# Support.net
KiCad netlist of a schematic drawn in Altium Designer
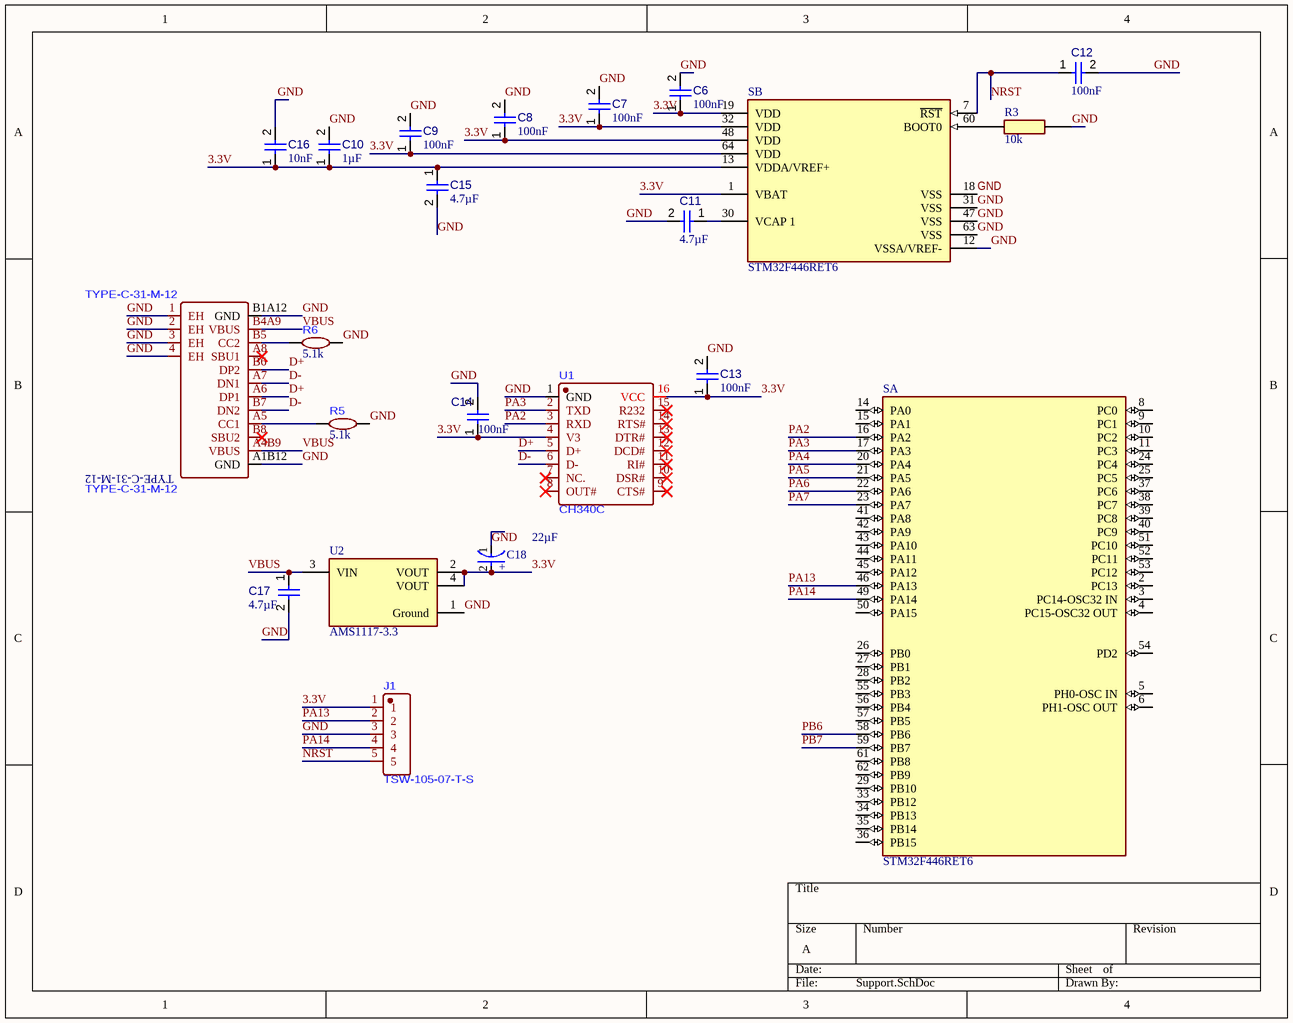
[diagram p0: Support.SchDoc]

(export (version "E")
  (design (tool "Eeschema 10.0.6"))
  (components
    (comp (ref "C6")
      (value "100nF")
      (footprint "CAPC1608X90X40NL10T20")
      (description "Chip Capacitor, 100 nF, +/- 10%, 50 V, 0603 (1608 Metric)")
      (fields (field (name "TOLERANCE") "10%") (field (name "Comment") "Capacitor 100 nF +/-10% 50 V 0603"))
      (libsource (lib "Jegasoth") (part "CAP-NP-2"))
    )
    (comp (ref "C7")
      (value "100nF")
      (footprint "CAPC1608X90X40NL10T20")
      (description "Chip Capacitor, 100 nF, +/- 10%, 50 V, 0603 (1608 Metric)")
      (fields (field (name "TOLERANCE") "10%") (field (name "Comment") "Capacitor 100 nF +/-10% 50 V 0603"))
      (libsource (lib "Jegasoth") (part "CAP-NP-2"))
    )
    (comp (ref "C8")
      (value "100nF")
      (footprint "CAPC1608X90X40NL10T20")
      (description "Chip Capacitor, 100 nF, +/- 10%, 50 V, 0603 (1608 Metric)")
      (fields (field (name "TOLERANCE") "10%") (field (name "Comment") "Capacitor 100 nF +/-10% 50 V 0603"))
      (libsource (lib "Jegasoth") (part "CAP-NP-2"))
    )
    (comp (ref "C9")
      (value "100nF")
      (footprint "CAPC1608X90X40NL10T20")
      (description "Chip Capacitor, 100 nF, +/- 10%, 50 V, 0603 (1608 Metric)")
      (fields (field (name "TOLERANCE") "10%") (field (name "Comment") "Capacitor 100 nF +/-10% 50 V 0603"))
      (libsource (lib "Jegasoth") (part "CAP-NP-2"))
    )
    (comp (ref "C10")
      (value "1µF")
      (footprint "CAPC0603(1608)100_L")
      (description "Chip Capacitor, 1µF +/-40%, 50V, 0603, Thickness 1 mm")
      (fields (field (name "TOLERANCE") "10%") (field (name "Comment") "Capacitor 1µF +/-40% 50V 0603"))
      (libsource (lib "Jegasoth") (part "CAP-NP-2"))
    )
    (comp (ref "C11")
      (value "4.7µF")
      (footprint "CAPC0603(1608)100_L")
      (description "Chip Capacitor, 4.7µF +/-20%, 10V, 0603, Thickness 1 mm")
      (fields (field (name "TOLERANCE") "10%") (field (name "Comment") "Capacitor 4.7µF +/-20% 10V 0603"))
      (libsource (lib "Jegasoth") (part "CAP-NP-2"))
    )
    (comp (ref "C12")
      (value "100nF")
      (footprint "CAPC1608X90X40NL10T20")
      (description "Chip Capacitor, 100 nF, +/- 10%, 50 V, 0603 (1608 Metric)")
      (fields (field (name "TOLERANCE") "10%") (field (name "Comment") "Capacitor 100 nF +/-10% 50 V 0603"))
      (libsource (lib "Jegasoth") (part "CAP-NP-2"))
    )
    (comp (ref "C13")
      (value "100nF")
      (footprint "CAPC1608X90X40NL10T20")
      (description "Chip Capacitor, 100 nF, +/- 10%, 50 V, 0603 (1608 Metric)")
      (fields (field (name "TOLERANCE") "10%") (field (name "Comment") "Capacitor 100 nF +/-10% 50 V 0603"))
      (libsource (lib "Jegasoth") (part "CAP-NP-2"))
    )
    (comp (ref "C14")
      (value "100nF")
      (footprint "CAPC1608X90X40NL10T20")
      (description "Chip Capacitor, 100 nF, +/- 10%, 50 V, 0603 (1608 Metric)")
      (fields (field (name "TOLERANCE") "10%") (field (name "Comment") "Capacitor 100 nF +/-10% 50 V 0603"))
      (libsource (lib "Jegasoth") (part "CAP-NP-2"))
    )
    (comp (ref "C15")
      (value "4.7µF")
      (footprint "CAPC0603(1608)100_L")
      (description "Chip Capacitor, 4.7µF +/-20%, 10V, 0603, Thickness 1 mm")
      (fields (field (name "TOLERANCE") "10%") (field (name "Comment") "Capacitor 4.7µF +/-20% 10V 0603"))
      (libsource (lib "Jegasoth") (part "CAP-NP-2"))
    )
    (comp (ref "C16")
      (value "10nF")
      (footprint "CAPC0402(1005)60_L")
      (description "Chip Capacitor, 10nF +/-20%, 50V, 0402, Thickness 0.6 mm")
      (fields (field (name "TOLERANCE") "5%") (field (name "Comment") "Capacitor 10nF +/-20% 50V 0402"))
      (libsource (lib "Jegasoth") (part "CAP-NP-2"))
    )
    (comp (ref "C17")
      (value "4.7µF")
      (footprint "CAPC0603(1608)100_L")
      (description "Chip Capacitor, 4.7µF +/-20%, 10V, 0603, Thickness 1 mm")
      (fields (field (name "TOLERANCE") "10%") (field (name "Comment") "Capacitor 4.7µF +/-20% 10V 0603"))
      (libsource (lib "Jegasoth") (part "CAP-NP-2"))
    )
    (comp (ref "C18")
      (value "22µF")
      (footprint "FP-TAJA-MFG")
      (description "Cap Tant Solid 22uF 10V A CASE 20%( 3.2 X 1.6 X 1.6mm) Inward L SMD 3216-18 3 Ohm 125C T/R")
      (fields (field (name "TOLERANCE") "20%") (field (name "VOLTAGE") "10V"))
      (libsource (lib "Jegasoth") (part "203bc49f2ac43e59fd269a8c329ed05"))
    )
    (comp (ref "J1")
      (value "TSW-105-07-T-S")
      (footprint "PCBComponent_1")
      (description "CONN HEADER VERT 5POS 2.54MM / Connector Header Through Hole 5 position 0.100\" (2.54mm)")
      (libsource (lib "Jegasoth") (part "TSW-105-07-T-S"))
    )
    (comp (ref "R3")
      (value "10k")
      (footprint "RESC1005X40N")
      (description "Res Thick Film 0402 10K Ohm 1% 0.063W(1/16W) ±100ppm/C Pad SMD T/R")
      (fields (field (name "TOLERANCE") "1%") (field (name "Comment") "0402WGF1002TCE"))
      (libsource (lib "Jegasoth") (part "0402WGF1002TCE"))
    )
    (comp (ref "R5")
      (value "5.1k")
      (footprint "PCBComponent_1")
      (description "Res Thick Film 0603 5.1K Ohm 1% 0.1W(1/10W) ±100ppm/C Pad SMD T/R")
      (fields (field (name "Comment") "0603WAF5101T5E"))
      (libsource (lib "Jegasoth") (part "0603WAF5101T5E"))
    )
    (comp (ref "R6")
      (value "5.1k")
      (footprint "PCBComponent_1")
      (description "Res Thick Film 0603 5.1K Ohm 1% 0.1W(1/10W) ±100ppm/C Pad SMD T/R")
      (fields (field (name "Comment") "0603WAF5101T5E"))
      (libsource (lib "Jegasoth") (part "0603WAF5101T5E"))
    )
    (comp (ref "S")
      (value "STM32F446RET6")
      (footprint "FP-LQFP64-5W-MFG")
      (description "MCU 32-bit ARM Cortex M4 RISC 512KB Flash 2.5V/3.3V Medical 64-Pin LQFP Frame")
      (libsource (lib "Jegasoth") (part "ee11adc32c0ab33b933cccf4348c338"))
    )
    (comp (ref "TYPE-C-31-M-12")
      (value "TYPE-C-31-M-12")
      (footprint "PCBComponent_1")
      (description "20V Type-C 1 16P Female head")
      (libsource (lib "Jegasoth") (part "TYPE-C-31-M-12_4"))
    )
    (comp (ref "U1")
      (value "CH340C")
      (footprint "PCBComponent_1")
      (description "uart to usb c")
      (libsource (lib "Jegasoth") (part "CH340C"))
    )
    (comp (ref "U2")
      (value "AMS1117-3.3")
      (footprint "FP-AMS1117-IPC_A")
      (libsource (lib "Jegasoth") (part "8bdbb5f8e77002000e30dd2845d0354"))
    )
  )
  (nets
    (net (code "1") (name "/3.3V") (class "Default")
      (node (ref "C10") (pin "1") (pinfunction "1_1") (pintype "passive"))
      (node (ref "C13") (pin "1") (pinfunction "1_1") (pintype "passive"))
      (node (ref "C14") (pin "1") (pinfunction "1_1") (pintype "passive"))
      (node (ref "C15") (pin "1") (pinfunction "1_1") (pintype "passive"))
      (node (ref "C16") (pin "1") (pinfunction "1_1") (pintype "passive"))
      (node (ref "C18") (pin "2") (pinfunction "A_2") (pintype "passive"))
      (node (ref "C6") (pin "1") (pinfunction "1_1") (pintype "passive"))
      (node (ref "C7") (pin "1") (pinfunction "1_1") (pintype "passive"))
      (node (ref "C8") (pin "1") (pinfunction "1_1") (pintype "passive"))
      (node (ref "C9") (pin "1") (pinfunction "1_1") (pintype "passive"))
      (node (ref "J1") (pin "1") (pinfunction "1_1") (pintype "passive"))
      (node (ref "S") (pin "1") (pinfunction "VBAT_1") (pintype "power_in"))
      (node (ref "S") (pin "13") (pinfunction "VDDA/VREF+_13") (pintype "power_in"))
      (node (ref "S") (pin "19") (pinfunction "VDD_19") (pintype "power_in"))
      (node (ref "S") (pin "32") (pinfunction "VDD_32") (pintype "power_in"))
      (node (ref "S") (pin "48") (pinfunction "VDD_48") (pintype "power_in"))
      (node (ref "S") (pin "64") (pinfunction "VDD_64") (pintype "power_in"))
      (node (ref "U1") (pin "16") (pinfunction "VCC_16") (pintype "passive"))
      (node (ref "U1") (pin "4") (pinfunction "V3_4") (pintype "passive"))
      (node (ref "U2") (pin "2") (pinfunction "VOUT_2") (pintype "passive"))
      (node (ref "U2") (pin "4") (pinfunction "VOUT_4") (pintype "passive"))
    )
    (net (code "2") (name "/D+") (class "Default")
      (node (ref "TYPE-C-31-M-12") (pin "A6") (pinfunction "DP1_A6") (pintype "passive"))
      (node (ref "TYPE-C-31-M-12") (pin "B6") (pinfunction "DP2_B6") (pintype "passive"))
      (node (ref "U1") (pin "5") (pinfunction "D+_5") (pintype "passive"))
    )
    (net (code "3") (name "/D-") (class "Default")
      (node (ref "TYPE-C-31-M-12") (pin "A7") (pinfunction "DN1_A7") (pintype "passive"))
      (node (ref "TYPE-C-31-M-12") (pin "B7") (pinfunction "DN2_B7") (pintype "passive"))
      (node (ref "U1") (pin "6") (pinfunction "D-_6") (pintype "passive"))
    )
    (net (code "4") (name "/GND") (class "Default")
      (node (ref "C10") (pin "2") (pinfunction "2_2") (pintype "passive"))
      (node (ref "C11") (pin "2") (pinfunction "2_2") (pintype "passive"))
      (node (ref "C12") (pin "2") (pinfunction "2_2") (pintype "passive"))
      (node (ref "C13") (pin "2") (pinfunction "2_2") (pintype "passive"))
      (node (ref "C14") (pin "2") (pinfunction "2_2") (pintype "passive"))
      (node (ref "C15") (pin "2") (pinfunction "2_2") (pintype "passive"))
      (node (ref "C16") (pin "2") (pinfunction "2_2") (pintype "passive"))
      (node (ref "C17") (pin "2") (pinfunction "2_2") (pintype "passive"))
      (node (ref "C18") (pin "1") (pinfunction "C_1") (pintype "passive"))
      (node (ref "C6") (pin "2") (pinfunction "2_2") (pintype "passive"))
      (node (ref "C7") (pin "2") (pinfunction "2_2") (pintype "passive"))
      (node (ref "C8") (pin "2") (pinfunction "2_2") (pintype "passive"))
      (node (ref "C9") (pin "2") (pinfunction "2_2") (pintype "passive"))
      (node (ref "J1") (pin "3") (pinfunction "3_3") (pintype "passive"))
      (node (ref "R3") (pin "2") (pinfunction "2_2") (pintype "passive"))
      (node (ref "R5") (pin "2") (pinfunction "2_2") (pintype "passive"))
      (node (ref "R6") (pin "2") (pinfunction "2_2") (pintype "passive"))
      (node (ref "S") (pin "12") (pinfunction "VSSA/VREF-_12") (pintype "power_in"))
      (node (ref "S") (pin "18") (pinfunction "VSS_18") (pintype "power_in"))
      (node (ref "S") (pin "31") (pinfunction "VSS_31") (pintype "power_in"))
      (node (ref "S") (pin "47") (pinfunction "VSS_47") (pintype "power_in"))
      (node (ref "S") (pin "63") (pinfunction "VSS_63") (pintype "power_in"))
      (node (ref "TYPE-C-31-M-12") (pin "1") (pinfunction "EH_1") (pintype "passive"))
      (node (ref "TYPE-C-31-M-12") (pin "2") (pinfunction "EH_2") (pintype "passive"))
      (node (ref "TYPE-C-31-M-12") (pin "3") (pinfunction "EH_3") (pintype "passive"))
      (node (ref "TYPE-C-31-M-12") (pin "4") (pinfunction "EH_4") (pintype "passive"))
      (node (ref "TYPE-C-31-M-12") (pin "A1B12") (pinfunction "GND_A1B12") (pintype "passive"))
      (node (ref "TYPE-C-31-M-12") (pin "B1A12") (pinfunction "GND_B1A12") (pintype "passive"))
      (node (ref "U1") (pin "1") (pinfunction "GND_1") (pintype "passive"))
      (node (ref "U2") (pin "1") (pinfunction "Ground_1") (pintype "power_in"))
    )
    (net (code "5") (name "/NRST") (class "Default")
      (node (ref "C12") (pin "1") (pinfunction "1_1") (pintype "passive"))
      (node (ref "J1") (pin "5") (pinfunction "5_5") (pintype "passive"))
      (node (ref "S") (pin "7") (pinfunction "~{RST}_7") (pintype "input"))
    )
    (net (code "6") (name "/PA2") (class "Default")
      (node (ref "S") (pin "16") (pinfunction "PA2_16") (pintype "bidirectional"))
      (node (ref "U1") (pin "3") (pinfunction "RXD_3") (pintype "passive"))
    )
    (net (code "7") (name "/PA3") (class "Default")
      (node (ref "S") (pin "17") (pinfunction "PA3_17") (pintype "bidirectional"))
      (node (ref "U1") (pin "2") (pinfunction "TXD_2") (pintype "passive"))
    )
    (net (code "8") (name "/PA4") (class "Default")
      (node (ref "S") (pin "20") (pinfunction "PA4_20") (pintype "bidirectional"))
    )
    (net (code "9") (name "/PA5") (class "Default")
      (node (ref "S") (pin "21") (pinfunction "PA5_21") (pintype "bidirectional"))
    )
    (net (code "10") (name "/PA6") (class "Default")
      (node (ref "S") (pin "22") (pinfunction "PA6_22") (pintype "bidirectional"))
    )
    (net (code "11") (name "/PA7") (class "Default")
      (node (ref "S") (pin "23") (pinfunction "PA7_23") (pintype "bidirectional"))
    )
    (net (code "12") (name "/PA13") (class "Default")
      (node (ref "J1") (pin "2") (pinfunction "2_2") (pintype "passive"))
      (node (ref "S") (pin "46") (pinfunction "PA13_46") (pintype "bidirectional"))
    )
    (net (code "13") (name "/PA14") (class "Default")
      (node (ref "J1") (pin "4") (pinfunction "4_4") (pintype "passive"))
      (node (ref "S") (pin "49") (pinfunction "PA14_49") (pintype "bidirectional"))
    )
    (net (code "14") (name "/PB6") (class "Default")
      (node (ref "S") (pin "58") (pinfunction "PB6_58") (pintype "bidirectional"))
    )
    (net (code "15") (name "/PB7") (class "Default")
      (node (ref "S") (pin "59") (pinfunction "PB7_59") (pintype "bidirectional"))
    )
    (net (code "16") (name "/VBUS") (class "Default")
      (node (ref "C17") (pin "1") (pinfunction "1_1") (pintype "passive"))
      (node (ref "TYPE-C-31-M-12") (pin "A4B9") (pinfunction "VBUS_A4B9") (pintype "passive"))
      (node (ref "TYPE-C-31-M-12") (pin "B4A9") (pinfunction "VBUS_B4A9") (pintype "passive"))
      (node (ref "U2") (pin "3") (pinfunction "VIN_3") (pintype "power_in"))
    )
    (net (code "17") (name "Net-(SB-BOOT0)") (class "Default")
      (node (ref "R3") (pin "1") (pinfunction "1_1") (pintype "passive"))
      (node (ref "S") (pin "60") (pinfunction "BOOT0_60") (pintype "input"))
    )
    (net (code "18") (name "Net-(SB-VCAP_1)") (class "Default")
      (node (ref "C11") (pin "1") (pinfunction "1_1") (pintype "passive"))
      (node (ref "S") (pin "30") (pinfunction "VCAP_1_30") (pintype "power_in"))
    )
    (net (code "19") (name "Net-(TYPE-C-31-M-12-CC1)") (class "Default")
      (node (ref "R5") (pin "1") (pinfunction "1_1") (pintype "passive"))
      (node (ref "TYPE-C-31-M-12") (pin "A5") (pinfunction "CC1_A5") (pintype "passive"))
    )
    (net (code "20") (name "Net-(TYPE-C-31-M-12-CC2)") (class "Default")
      (node (ref "R6") (pin "1") (pinfunction "1_1") (pintype "passive"))
      (node (ref "TYPE-C-31-M-12") (pin "B5") (pinfunction "CC2_B5") (pintype "passive"))
    )
    (net (code "21") (name "unconnected-(SA-PA0-Pad14)") (class "Default")
      (node (ref "S") (pin "14") (pinfunction "PA0_14") (pintype "bidirectional"))
    )
    (net (code "22") (name "unconnected-(SA-PA1-Pad15)") (class "Default")
      (node (ref "S") (pin "15") (pinfunction "PA1_15") (pintype "bidirectional"))
    )
    (net (code "23") (name "unconnected-(SA-PA8-Pad41)") (class "Default")
      (node (ref "S") (pin "41") (pinfunction "PA8_41") (pintype "bidirectional"))
    )
    (net (code "24") (name "unconnected-(SA-PA9-Pad42)") (class "Default")
      (node (ref "S") (pin "42") (pinfunction "PA9_42") (pintype "bidirectional"))
    )
    (net (code "25") (name "unconnected-(SA-PA10-Pad43)") (class "Default")
      (node (ref "S") (pin "43") (pinfunction "PA10_43") (pintype "bidirectional"))
    )
    (net (code "26") (name "unconnected-(SA-PA11-Pad44)") (class "Default")
      (node (ref "S") (pin "44") (pinfunction "PA11_44") (pintype "bidirectional"))
    )
    (net (code "27") (name "unconnected-(SA-PA12-Pad45)") (class "Default")
      (node (ref "S") (pin "45") (pinfunction "PA12_45") (pintype "bidirectional"))
    )
    (net (code "28") (name "unconnected-(SA-PA15-Pad50)") (class "Default")
      (node (ref "S") (pin "50") (pinfunction "PA15_50") (pintype "bidirectional"))
    )
    (net (code "29") (name "unconnected-(SA-PB0-Pad26)") (class "Default")
      (node (ref "S") (pin "26") (pinfunction "PB0_26") (pintype "bidirectional"))
    )
    (net (code "30") (name "unconnected-(SA-PB1-Pad27)") (class "Default")
      (node (ref "S") (pin "27") (pinfunction "PB1_27") (pintype "bidirectional"))
    )
    (net (code "31") (name "unconnected-(SA-PB2-Pad28)") (class "Default")
      (node (ref "S") (pin "28") (pinfunction "PB2_28") (pintype "bidirectional"))
    )
    (net (code "32") (name "unconnected-(SA-PB3-Pad55)") (class "Default")
      (node (ref "S") (pin "55") (pinfunction "PB3_55") (pintype "bidirectional"))
    )
    (net (code "33") (name "unconnected-(SA-PB4-Pad56)") (class "Default")
      (node (ref "S") (pin "56") (pinfunction "PB4_56") (pintype "bidirectional"))
    )
    (net (code "34") (name "unconnected-(SA-PB5-Pad57)") (class "Default")
      (node (ref "S") (pin "57") (pinfunction "PB5_57") (pintype "bidirectional"))
    )
    (net (code "35") (name "unconnected-(SA-PB8-Pad61)") (class "Default")
      (node (ref "S") (pin "61") (pinfunction "PB8_61") (pintype "bidirectional"))
    )
    (net (code "36") (name "unconnected-(SA-PB9-Pad62)") (class "Default")
      (node (ref "S") (pin "62") (pinfunction "PB9_62") (pintype "bidirectional"))
    )
    (net (code "37") (name "unconnected-(SA-PB10-Pad29)") (class "Default")
      (node (ref "S") (pin "29") (pinfunction "PB10_29") (pintype "bidirectional"))
    )
    (net (code "38") (name "unconnected-(SA-PB12-Pad33)") (class "Default")
      (node (ref "S") (pin "33") (pinfunction "PB12_33") (pintype "bidirectional"))
    )
    (net (code "39") (name "unconnected-(SA-PB13-Pad34)") (class "Default")
      (node (ref "S") (pin "34") (pinfunction "PB13_34") (pintype "bidirectional"))
    )
    (net (code "40") (name "unconnected-(SA-PB14-Pad35)") (class "Default")
      (node (ref "S") (pin "35") (pinfunction "PB14_35") (pintype "bidirectional"))
    )
    (net (code "41") (name "unconnected-(SA-PB15-Pad36)") (class "Default")
      (node (ref "S") (pin "36") (pinfunction "PB15_36") (pintype "bidirectional"))
    )
    (net (code "42") (name "unconnected-(SA-PC0-Pad8)") (class "Default")
      (node (ref "S") (pin "8") (pinfunction "PC0_8") (pintype "bidirectional"))
    )
    (net (code "43") (name "unconnected-(SA-PC1-Pad9)") (class "Default")
      (node (ref "S") (pin "9") (pinfunction "PC1_9") (pintype "bidirectional"))
    )
    (net (code "44") (name "unconnected-(SA-PC2-Pad10)") (class "Default")
      (node (ref "S") (pin "10") (pinfunction "PC2_10") (pintype "bidirectional"))
    )
    (net (code "45") (name "unconnected-(SA-PC3-Pad11)") (class "Default")
      (node (ref "S") (pin "11") (pinfunction "PC3_11") (pintype "bidirectional"))
    )
    (net (code "46") (name "unconnected-(SA-PC4-Pad24)") (class "Default")
      (node (ref "S") (pin "24") (pinfunction "PC4_24") (pintype "bidirectional"))
    )
    (net (code "47") (name "unconnected-(SA-PC5-Pad25)") (class "Default")
      (node (ref "S") (pin "25") (pinfunction "PC5_25") (pintype "bidirectional"))
    )
    (net (code "48") (name "unconnected-(SA-PC6-Pad37)") (class "Default")
      (node (ref "S") (pin "37") (pinfunction "PC6_37") (pintype "bidirectional"))
    )
    (net (code "49") (name "unconnected-(SA-PC7-Pad38)") (class "Default")
      (node (ref "S") (pin "38") (pinfunction "PC7_38") (pintype "bidirectional"))
    )
    (net (code "50") (name "unconnected-(SA-PC8-Pad39)") (class "Default")
      (node (ref "S") (pin "39") (pinfunction "PC8_39") (pintype "bidirectional"))
    )
    (net (code "51") (name "unconnected-(SA-PC9-Pad40)") (class "Default")
      (node (ref "S") (pin "40") (pinfunction "PC9_40") (pintype "bidirectional"))
    )
    (net (code "52") (name "unconnected-(SA-PC10-Pad51)") (class "Default")
      (node (ref "S") (pin "51") (pinfunction "PC10_51") (pintype "bidirectional"))
    )
    (net (code "53") (name "unconnected-(SA-PC11-Pad52)") (class "Default")
      (node (ref "S") (pin "52") (pinfunction "PC11_52") (pintype "bidirectional"))
    )
    (net (code "54") (name "unconnected-(SA-PC12-Pad53)") (class "Default")
      (node (ref "S") (pin "53") (pinfunction "PC12_53") (pintype "bidirectional"))
    )
    (net (code "55") (name "unconnected-(SA-PC13-Pad2)") (class "Default")
      (node (ref "S") (pin "2") (pinfunction "PC13_2") (pintype "bidirectional"))
    )
    (net (code "56") (name "unconnected-(SA-PC14-OSC32_IN-Pad3)") (class "Default")
      (node (ref "S") (pin "3") (pinfunction "PC14-OSC32_IN_3") (pintype "bidirectional"))
    )
    (net (code "57") (name "unconnected-(SA-PC15-OSC32_OUT-Pad4)") (class "Default")
      (node (ref "S") (pin "4") (pinfunction "PC15-OSC32_OUT_4") (pintype "bidirectional"))
    )
    (net (code "58") (name "unconnected-(SA-PD2-Pad54)") (class "Default")
      (node (ref "S") (pin "54") (pinfunction "PD2_54") (pintype "bidirectional"))
    )
    (net (code "59") (name "unconnected-(SA-PH0-OSC_IN-Pad5)") (class "Default")
      (node (ref "S") (pin "5") (pinfunction "PH0-OSC_IN_5") (pintype "bidirectional"))
    )
    (net (code "60") (name "unconnected-(SA-PH1-OSC_OUT-Pad6)") (class "Default")
      (node (ref "S") (pin "6") (pinfunction "PH1-OSC_OUT_6") (pintype "bidirectional"))
    )
    (net (code "61") (name "unconnected-(TYPE-C-31-M-12-SBU1-PadA8)") (class "Default")
      (node (ref "TYPE-C-31-M-12") (pin "A8") (pinfunction "SBU1_A8") (pintype "passive+no_connect"))
    )
    (net (code "62") (name "unconnected-(TYPE-C-31-M-12-SBU2-PadB8)") (class "Default")
      (node (ref "TYPE-C-31-M-12") (pin "B8") (pinfunction "SBU2_B8") (pintype "passive+no_connect"))
    )
    (net (code "63") (name "unconnected-(U1-CTS#-Pad9)") (class "Default")
      (node (ref "U1") (pin "9") (pinfunction "CTS#_9") (pintype "passive+no_connect"))
    )
    (net (code "64") (name "unconnected-(U1-DCD#-Pad12)") (class "Default")
      (node (ref "U1") (pin "12") (pinfunction "DCD#_12") (pintype "passive+no_connect"))
    )
    (net (code "65") (name "unconnected-(U1-DSR#-Pad10)") (class "Default")
      (node (ref "U1") (pin "10") (pinfunction "DSR#_10") (pintype "passive+no_connect"))
    )
    (net (code "66") (name "unconnected-(U1-DTR#-Pad13)") (class "Default")
      (node (ref "U1") (pin "13") (pinfunction "DTR#_13") (pintype "passive+no_connect"))
    )
    (net (code "67") (name "unconnected-(U1-NC.-Pad7)") (class "Default")
      (node (ref "U1") (pin "7") (pinfunction "NC._7") (pintype "passive+no_connect"))
    )
    (net (code "68") (name "unconnected-(U1-OUT#-Pad8)") (class "Default")
      (node (ref "U1") (pin "8") (pinfunction "OUT#_8") (pintype "passive+no_connect"))
    )
    (net (code "69") (name "unconnected-(U1-R232-Pad15)") (class "Default")
      (node (ref "U1") (pin "15") (pinfunction "R232_15") (pintype "passive+no_connect"))
    )
    (net (code "70") (name "unconnected-(U1-RI#-Pad11)") (class "Default")
      (node (ref "U1") (pin "11") (pinfunction "RI#_11") (pintype "passive+no_connect"))
    )
    (net (code "71") (name "unconnected-(U1-RTS#-Pad14)") (class "Default")
      (node (ref "U1") (pin "14") (pinfunction "RTS#_14") (pintype "passive+no_connect"))
    )
  )
)
